# samd21_actuatorhub_pro_1_0_1_may2023.net
KiCad netlist of a schematic drawn in EAGLE
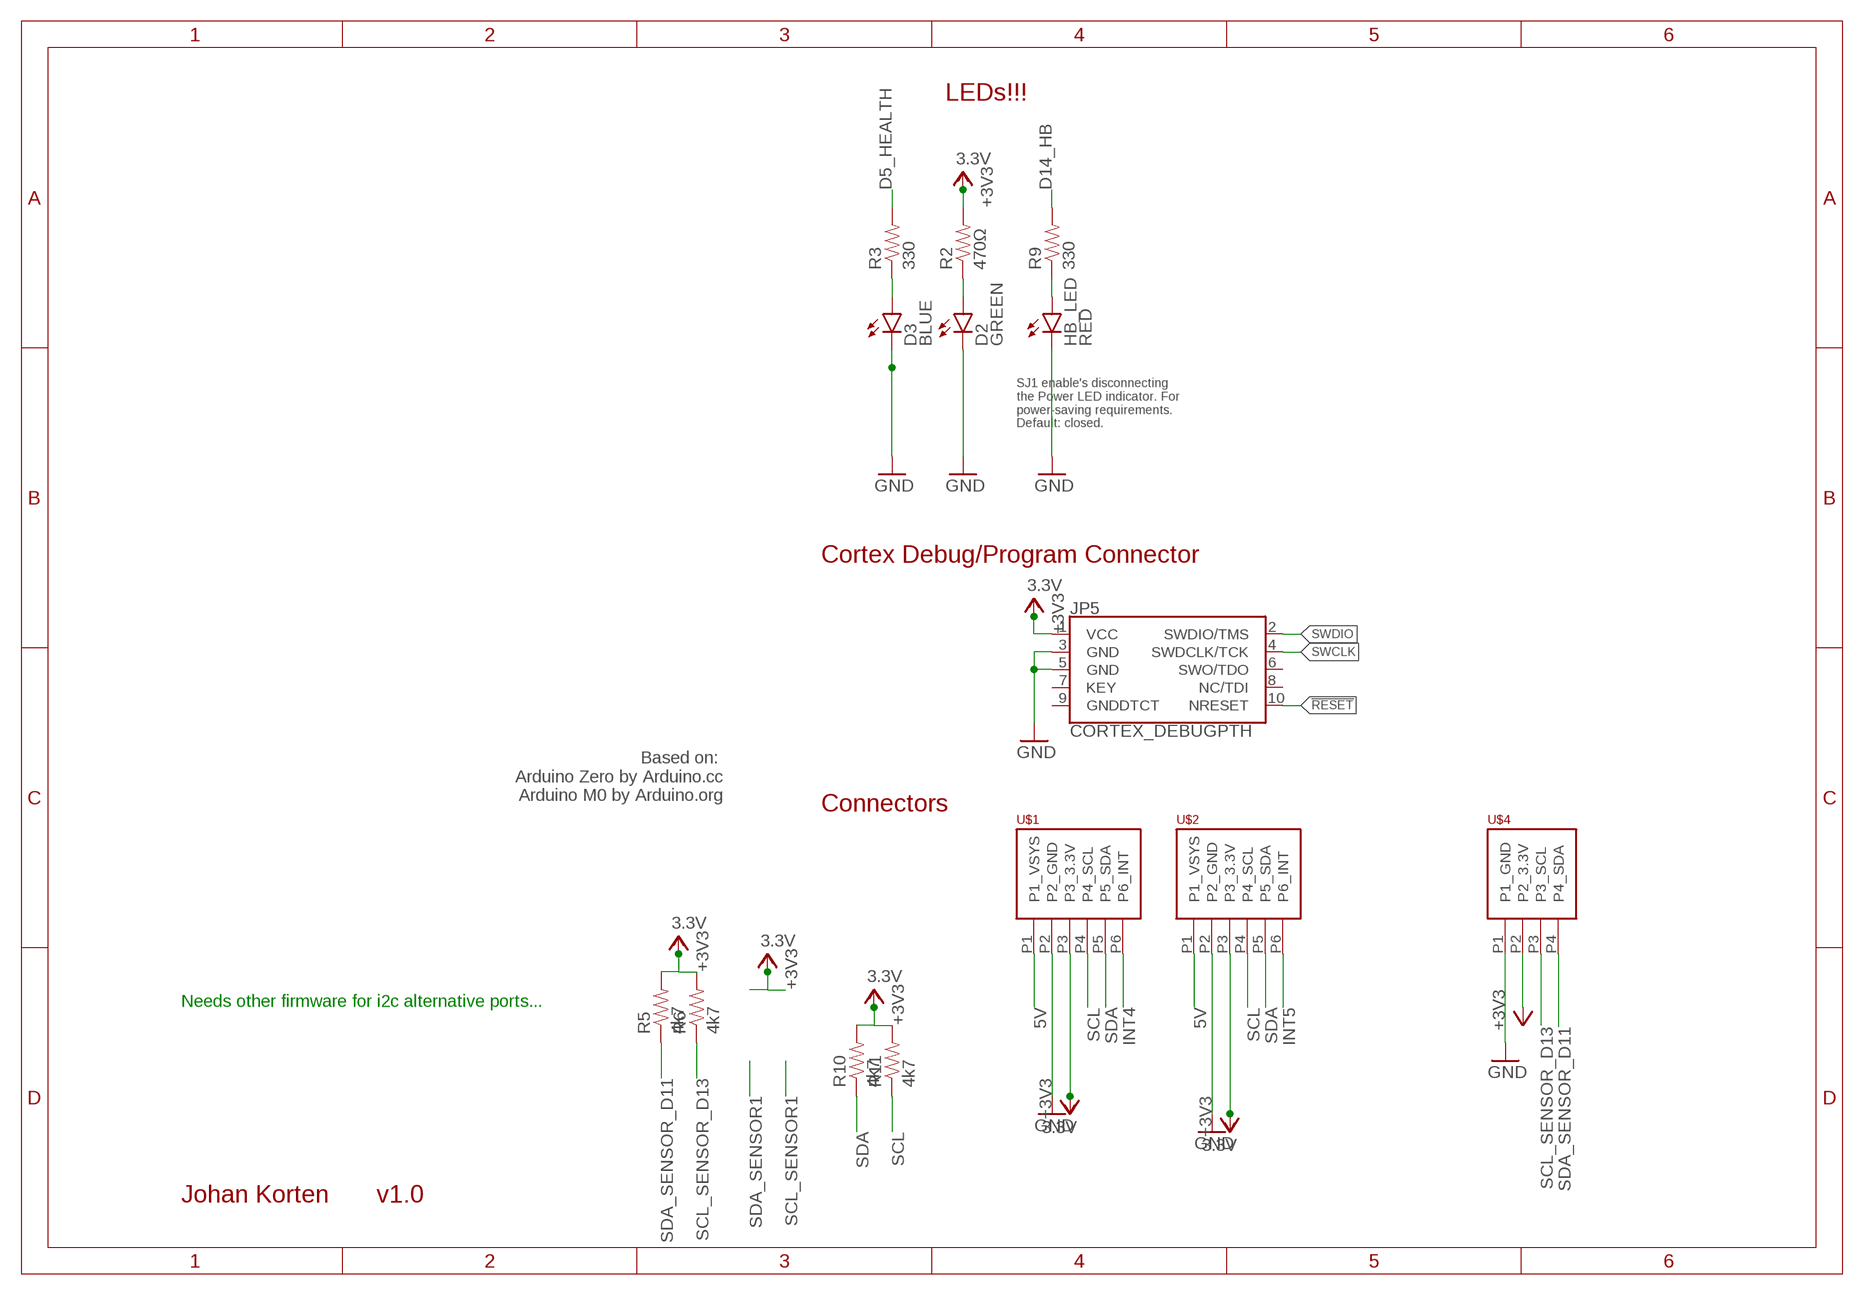
[diagram p0: schematic, sheet 1]
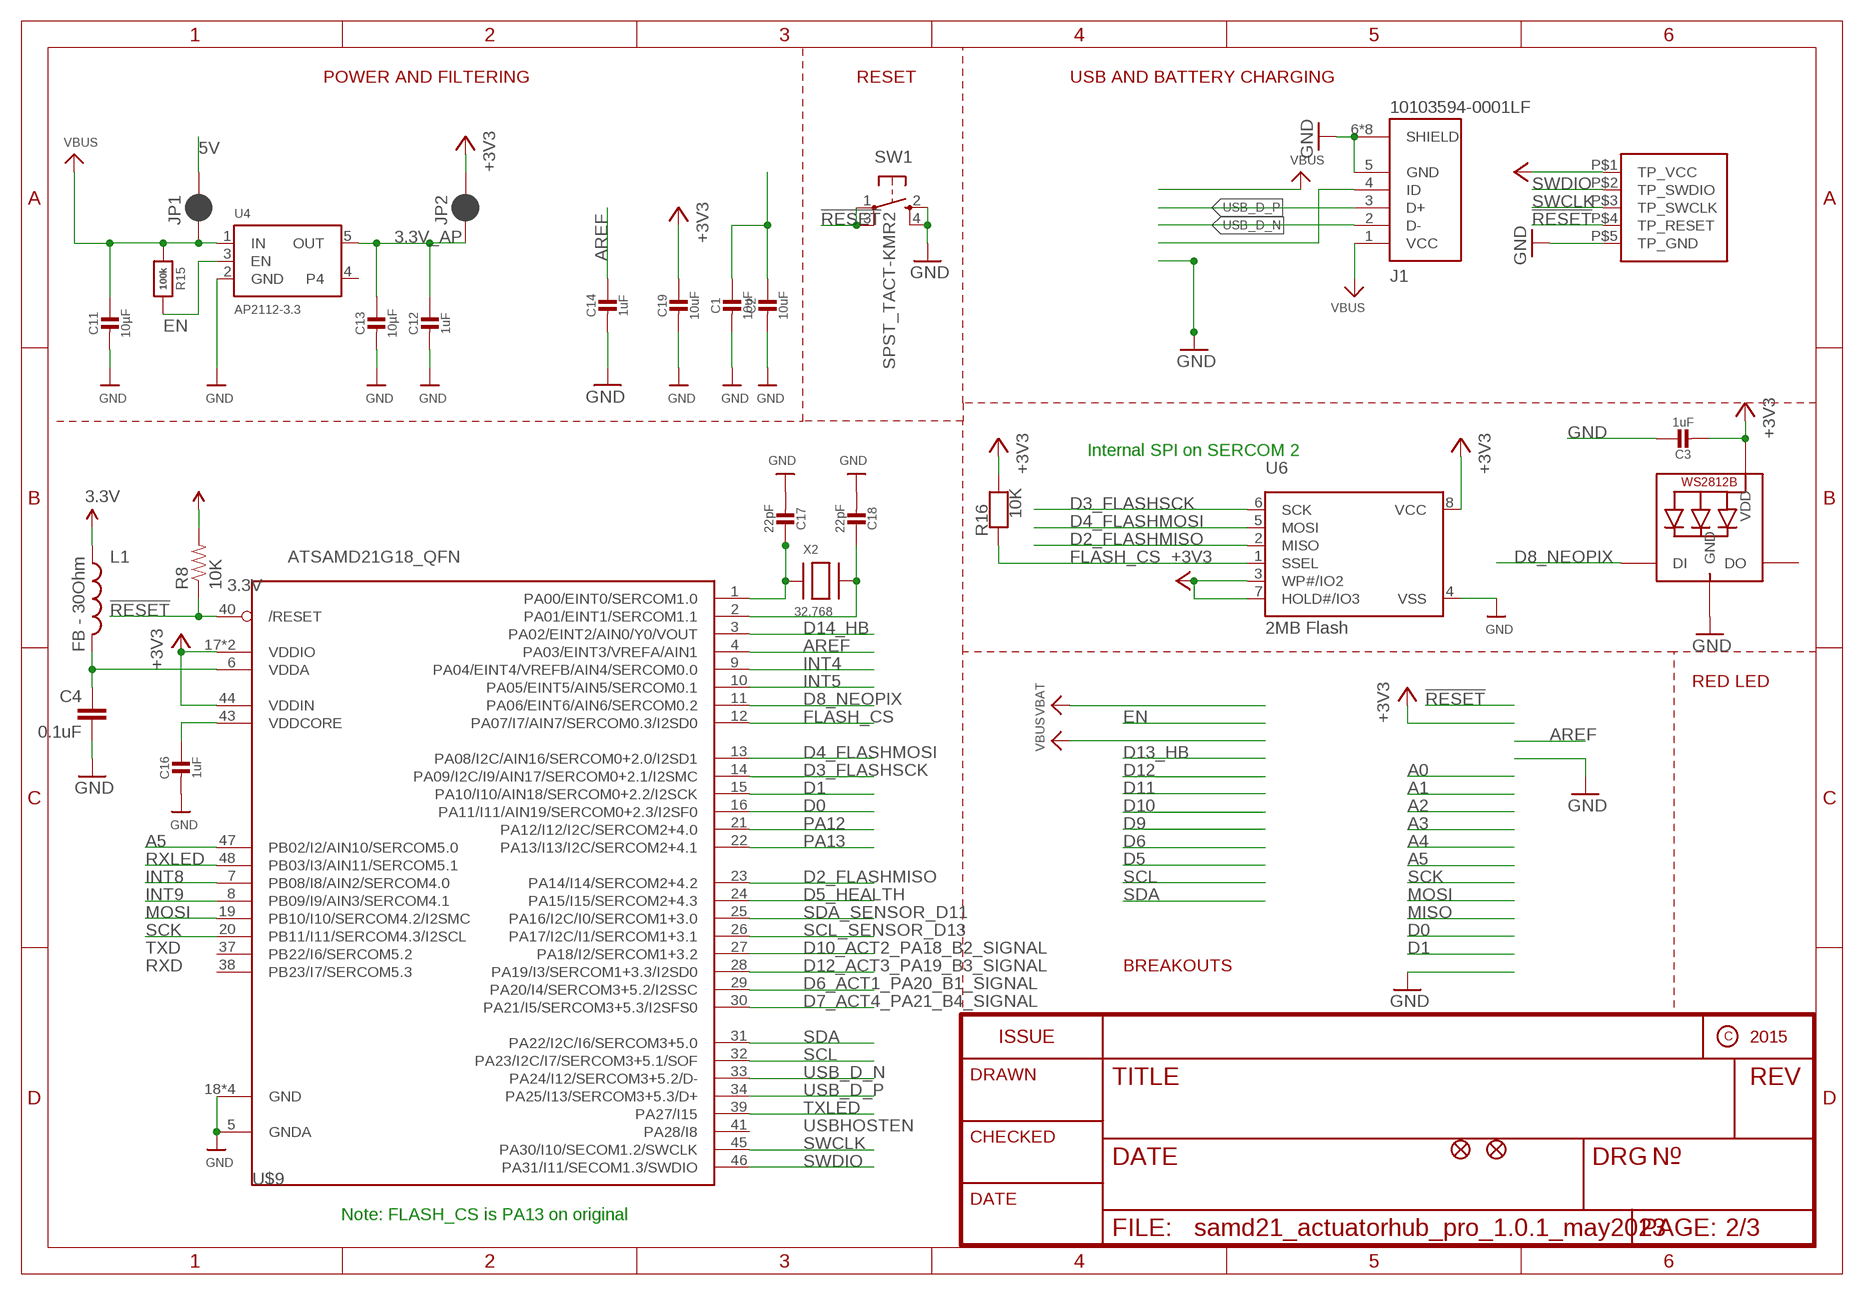
[diagram p1: schematic, sheet 2]
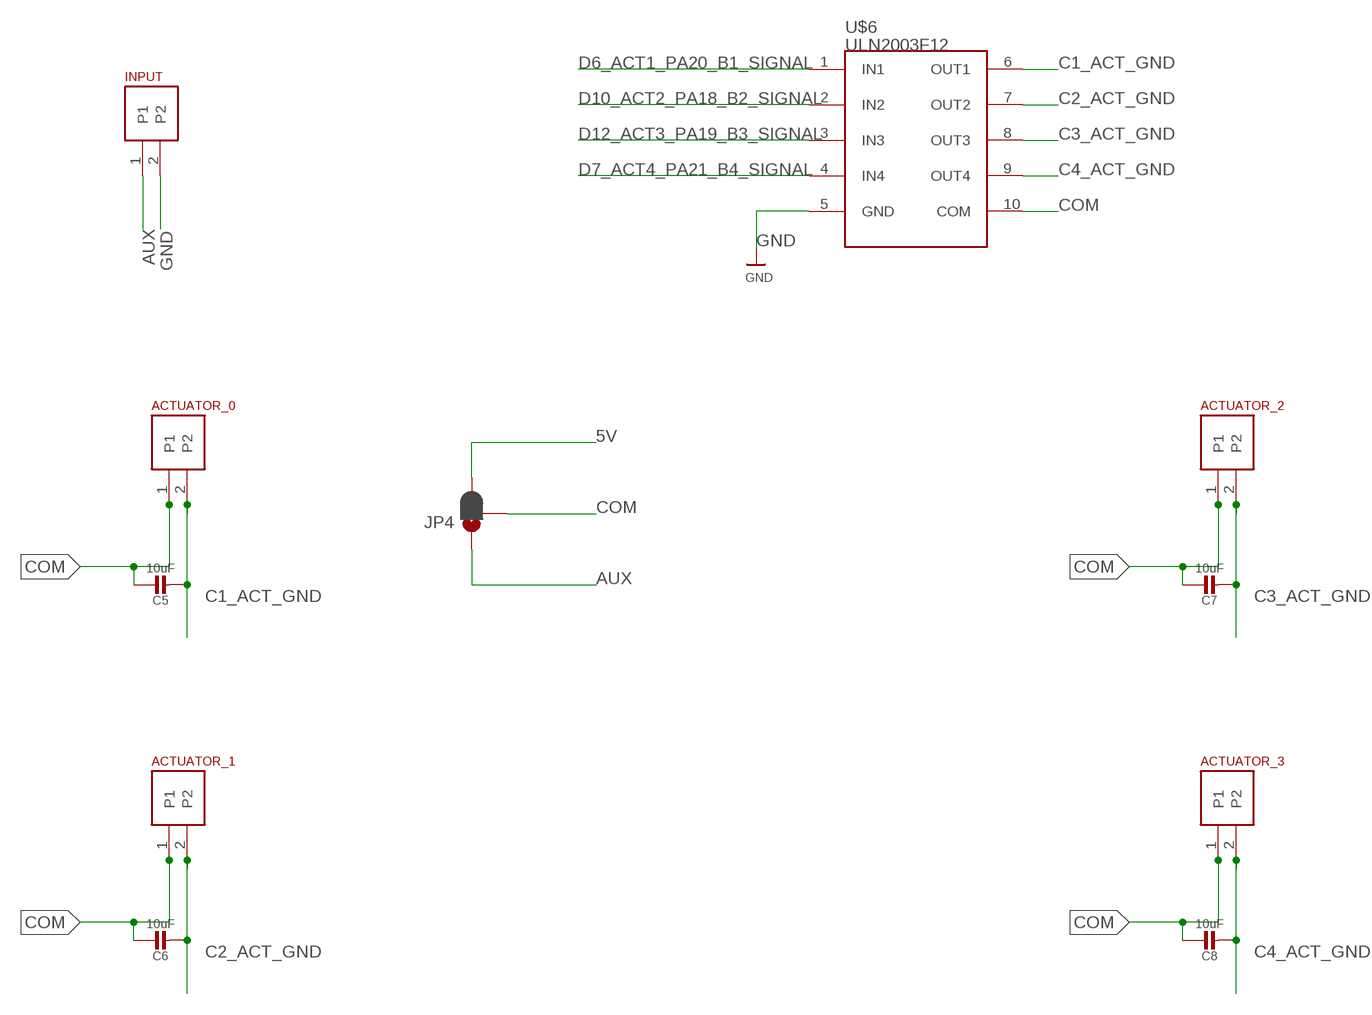
[diagram p2: schematic, sheet 3]

(export (version "E")
  (design (tool "Eeschema 10.0.6"))
  (components
    (comp (ref "ACTUATOR_0")
      (value "PHOENIX_PTSM_M2_TH")
      (footprint "eagle-import:PTSM_M2_THRHOLE")
      (libsource (lib "eagle-import") (part "PHOENIX_PTSM_M2_TH"))
    )
    (comp (ref "ACTUATOR_1")
      (value "PHOENIX_PTSM_M2_TH")
      (footprint "eagle-import:PTSM_M2_THRHOLE")
      (libsource (lib "eagle-import") (part "PHOENIX_PTSM_M2_TH"))
    )
    (comp (ref "ACTUATOR_2")
      (value "PHOENIX_PTSM_M2TH")
      (footprint "eagle-import:PTSM_M2_THRHOLE")
      (libsource (lib "eagle-import") (part "PHOENIX_PTSM_M2TH"))
    )
    (comp (ref "ACTUATOR_3")
      (value "PHOENIX_PTSM_M2TH")
      (footprint "eagle-import:PTSM_M2_THRHOLE")
      (libsource (lib "eagle-import") (part "PHOENIX_PTSM_M2TH"))
    )
    (comp (ref "C5")
      (value "10uF")
      (footprint "eagle-import:0805-NO")
      (libsource (lib "eagle-import") (part "CAP_CERAMIC0805-NOOUTLINE"))
    )
    (comp (ref "C6")
      (value "10uF")
      (footprint "eagle-import:0805-NO")
      (libsource (lib "eagle-import") (part "CAP_CERAMIC0805-NOOUTLINE"))
    )
    (comp (ref "C7")
      (value "10uF")
      (footprint "eagle-import:0805-NO")
      (libsource (lib "eagle-import") (part "CAP_CERAMIC0805-NOOUTLINE"))
    )
    (comp (ref "C8")
      (value "10uF")
      (footprint "eagle-import:0805-NO")
      (libsource (lib "eagle-import") (part "CAP_CERAMIC0805-NOOUTLINE"))
    )
    (comp (ref "INPUT")
      (value "PHOENIX_PTSM_M2_TH")
      (footprint "eagle-import:PTSM_M2_THRHOLE")
      (libsource (lib "eagle-import") (part "PHOENIX_PTSM_M2_TH"))
    )
    (comp (ref "JP4")
      (value "JUMPER-SMT_3_1-NC_PASTE_SILK")
      (footprint "eagle-import:SMT-JUMPER_3_1-NC_PASTE_SILK")
      (libsource (lib "eagle-import") (part "JUMPER-SMT_3_1-NC_PASTE_SILK"))
    )
    (comp (ref "U$6")
      (value "ULN2003F12")
      (footprint "eagle-import:U-DFN3030-10")
      (fields (field (name "MF") "Diodes Zetex"))
      (libsource (lib "eagle-import") (part "ULN2003F12"))
    )
    (comp (ref "D2")
      (value "GREEN")
      (footprint "eagle-import:LED-0603")
      (libsource (lib "eagle-import") (part "LED-RED0603"))
    )
    (comp (ref "D3")
      (value "BLUE")
      (footprint "eagle-import:LED-0603")
      (libsource (lib "eagle-import") (part "LED-BLUE0603"))
    )
    (comp (ref "HB_LED")
      (value "RED")
      (footprint "eagle-import:LED-0603")
      (libsource (lib "eagle-import") (part "LED-RED0603"))
    )
    (comp (ref "JP5")
      (value "CORTEX_DEBUGPTH")
      (footprint "eagle-import:2X5-PTH-1.27MM")
      (libsource (lib "eagle-import") (part "CORTEX_DEBUGPTH"))
    )
    (comp (ref "R2")
      (value "470Ω")
      (footprint "eagle-import:0603-RES")
      (libsource (lib "eagle-import") (part "330OHM1/10W1%(0603)"))
    )
    (comp (ref "R3")
      (value "330")
      (footprint "eagle-import:0603-RES")
      (libsource (lib "eagle-import") (part "330OHM1/10W1%(0603)"))
    )
    (comp (ref "R5")
      (value "4k7")
      (footprint "eagle-import:0603-RES")
      (libsource (lib "eagle-import") (part "330OHM1/10W1%(0603)"))
    )
    (comp (ref "R6")
      (value "4k7")
      (footprint "eagle-import:0603-RES")
      (libsource (lib "eagle-import") (part "330OHM1/10W1%(0603)"))
    )
    (comp (ref "R9")
      (value "330")
      (footprint "eagle-import:0603-RES")
      (libsource (lib "eagle-import") (part "330OHM1/10W1%(0603)"))
    )
    (comp (ref "R10")
      (value "4k7")
      (footprint "eagle-import:0603-RES")
      (libsource (lib "eagle-import") (part "330OHM1/10W1%(0603)"))
    )
    (comp (ref "R11")
      (value "4k7")
      (footprint "eagle-import:0603-RES")
      (libsource (lib "eagle-import") (part "330OHM1/10W1%(0603)"))
    )
    (comp (ref "U$1")
      (value "PHOENIX_PTSM_M6_TH_I2CPPANGLE")
      (footprint "eagle-import:PTSM_M6_THRHOLE")
      (libsource (lib "eagle-import") (part "PHOENIX_PTSM_M6_TH_I2CPPANGLE"))
    )
    (comp (ref "U$2")
      (value "PHOENIX_PTSM_M6_TH_I2CPPANGLE")
      (footprint "eagle-import:PTSM_M6_THRHOLE")
      (libsource (lib "eagle-import") (part "PHOENIX_PTSM_M6_TH_I2CPPANGLE"))
    )
    (comp (ref "U$4")
      (value "PHOENIX_PTSM_M4_THANGLE")
      (footprint "eagle-import:PTSM_M4_TH")
      (libsource (lib "eagle-import") (part "PHOENIX_PTSM_M4_THANGLE"))
    )
    (comp (ref "C1")
      (value "10uF")
      (footprint "eagle-import:0805-NO")
      (libsource (lib "eagle-import") (part "CAP_CERAMIC0805-NOOUTLINE"))
    )
    (comp (ref "C2")
      (value "10uF")
      (footprint "eagle-import:0805-NO")
      (libsource (lib "eagle-import") (part "CAP_CERAMIC0805-NOOUTLINE"))
    )
    (comp (ref "C3")
      (value "1uF")
      (footprint "eagle-import:0603-NO")
      (libsource (lib "eagle-import") (part "CAP_CERAMIC0603_NO"))
    )
    (comp (ref "C4")
      (value "0.1uF")
      (footprint "eagle-import:0402-CAP")
      (libsource (lib "eagle-import") (part "0.1UF-16V(+-10%)(0402)"))
    )
    (comp (ref "C11")
      (value "10µF")
      (footprint "eagle-import:0805-NO")
      (libsource (lib "eagle-import") (part "CAP_CERAMIC0805-NOOUTLINE"))
    )
    (comp (ref "C12")
      (value "1uF")
      (footprint "eagle-import:0603-NO")
      (libsource (lib "eagle-import") (part "CAP_CERAMIC0603_NO"))
    )
    (comp (ref "C13")
      (value "10µF")
      (footprint "eagle-import:0805-NO")
      (libsource (lib "eagle-import") (part "CAP_CERAMIC0805-NOOUTLINE"))
    )
    (comp (ref "C14")
      (value "1uF")
      (footprint "eagle-import:0603-NO")
      (libsource (lib "eagle-import") (part "CAP_CERAMIC0603_NO"))
    )
    (comp (ref "C16")
      (value "1uF")
      (footprint "eagle-import:0603-NO")
      (libsource (lib "eagle-import") (part "CAP_CERAMIC0603_NO"))
    )
    (comp (ref "C17")
      (value "22pF")
      (footprint "eagle-import:0603-NO")
      (libsource (lib "eagle-import") (part "CAP_CERAMIC0603_NO"))
    )
    (comp (ref "C18")
      (value "22pF")
      (footprint "eagle-import:0603-NO")
      (libsource (lib "eagle-import") (part "CAP_CERAMIC0603_NO"))
    )
    (comp (ref "C19")
      (value "10uF")
      (footprint "eagle-import:0805-NO")
      (libsource (lib "eagle-import") (part "CAP_CERAMIC0805-NOOUTLINE"))
    )
    (comp (ref "J1")
      (value "10103594-0001LF")
      (footprint "eagle-import:AMPHENOL_10103594-0001LF")
      (fields (field (name "MF") "AMPHENOL ICC / FCI"))
      (libsource (lib "eagle-import") (part "10103594-0001LF"))
    )
    (comp (ref "JP1")
      (value "JUMPER-SMT_2_NC_PASTE_SILK")
      (footprint "eagle-import:SMT-JUMPER_2_NC_PASTE_SILK")
      (libsource (lib "eagle-import") (part "JUMPER-SMT_2_NC_PASTE_SILK"))
    )
    (comp (ref "JP2")
      (value "JUMPER-SMT_2_NC_PASTE_SILK")
      (footprint "eagle-import:SMT-JUMPER_2_NC_PASTE_SILK")
      (libsource (lib "eagle-import") (part "JUMPER-SMT_2_NC_PASTE_SILK"))
    )
    (comp (ref "L1")
      (value "FB - 30Ohm")
      (footprint "eagle-import:0603")
      (libsource (lib "eagle-import") (part "INDUCTOR0603"))
    )
    (comp (ref "LED1")
      (value "WS2812B3535")
      (footprint "eagle-import:LED3535")
      (libsource (lib "eagle-import") (part "WS2812B3535"))
    )
    (comp (ref "R8")
      (value "10K")
      (footprint "eagle-import:0603-RES")
      (libsource (lib "eagle-import") (part "10KOHM-1/10W-1%(0603)0603"))
    )
    (comp (ref "R15")
      (value "100k")
      (footprint "eagle-import:0603-NO")
      (libsource (lib "eagle-import") (part "RESISTOR_0603_NOOUT"))
    )
    (comp (ref "R16")
      (value "10K")
      (footprint "eagle-import:0603-NO")
      (libsource (lib "eagle-import") (part "RESISTOR_0603_NOOUT"))
    )
    (comp (ref "SW1")
      (value "SPST_TACT-KMR2")
      (footprint "eagle-import:KMR2")
      (libsource (lib "eagle-import") (part "SPST_TACT-KMR2"))
    )
    (comp (ref "U$5")
      (value "HUB_TESTPINSHUBS")
      (footprint "eagle-import:TEST_PINS")
      (libsource (lib "eagle-import") (part "HUB_TESTPINSHUBS"))
    )
    (comp (ref "U$9")
      (value "ATSAMD21G18_QFN")
      (footprint "eagle-import:TQFN48_7MM")
      (libsource (lib "eagle-import") (part "ATSAMD21G_QFN"))
    )
    (comp (ref "U$34")
      (value "FIDUCIAL\"\"")
      (footprint "eagle-import:FIDUCIAL_1MM")
      (libsource (lib "eagle-import") (part "FIDUCIAL{dblquote}{dblquote}"))
    )
    (comp (ref "U$35")
      (value "FIDUCIAL\"\"")
      (footprint "eagle-import:FIDUCIAL_1MM")
      (libsource (lib "eagle-import") (part "FIDUCIAL{dblquote}{dblquote}"))
    )
    (comp (ref "U4")
      (value "AP2112-3.3")
      (footprint "eagle-import:SOT23-5")
      (libsource (lib "eagle-import") (part "VREG_SOT23-5"))
    )
    (comp (ref "U6")
      (value "2MB Flash")
      (footprint "eagle-import:SOIC8_208MIL")
      (libsource (lib "eagle-import") (part "SPIFLASH_SOIC8208MIL"))
    )
    (comp (ref "X2")
      (value "32.768")
      (footprint "eagle-import:XTAL3215")
      (libsource (lib "eagle-import") (part "XTAL-3.2X1.5"))
    )
  )
  (nets
    (net (code "1") (name "+3V3") (class "Default")
      (node (ref "C19") (pin "1") (pinfunction "1_1") (pintype "passive"))
      (node (ref "C3") (pin "2") (pinfunction "2_2") (pintype "passive"))
      (node (ref "JP2") (pin "2") (pinfunction "2_2") (pintype "passive"))
      (node (ref "JP5") (pin "1") (pinfunction "VCC_1") (pintype "bidirectional"))
      (node (ref "L1") (pin "1") (pinfunction "1_1") (pintype "passive"))
      (node (ref "LED1") (pin "2") (pinfunction "VDD_2") (pintype "power_in"))
      (node (ref "R10") (pin "2") (pinfunction "2_2") (pintype "passive"))
      (node (ref "R11") (pin "2") (pinfunction "2_2") (pintype "passive"))
      (node (ref "R16") (pin "2") (pinfunction "2_2") (pintype "passive"))
      (node (ref "R2") (pin "2") (pinfunction "2_2") (pintype "passive"))
      (node (ref "R5") (pin "2") (pinfunction "2_2") (pintype "passive"))
      (node (ref "R6") (pin "2") (pinfunction "2_2") (pintype "passive"))
      (node (ref "R8") (pin "2") (pinfunction "2_2") (pintype "passive"))
      (node (ref "U$1") (pin "P3") (pinfunction "P3_3.3V_P3") (pintype "power_in"))
      (node (ref "U$2") (pin "P3") (pinfunction "P3_3.3V_P3") (pintype "power_in"))
      (node (ref "U$4") (pin "P2") (pinfunction "P2_3.3V_P2") (pintype "power_in"))
      (node (ref "U$5") (pin "P$1") (pinfunction "TP_VCC_P$1") (pintype "bidirectional"))
      (node (ref "U$9") (pin "17") (pinfunction "VDDIO_17") (pintype "power_in"))
      (node (ref "U$9") (pin "36") (pinfunction "VDDIO_36") (pintype "power_in"))
      (node (ref "U$9") (pin "44") (pinfunction "VDDIN_44") (pintype "power_in"))
      (node (ref "U6") (pin "3") (pinfunction "WP#/IO2_3") (pintype "bidirectional"))
      (node (ref "U6") (pin "7") (pinfunction "HOLD#/IO3_7") (pintype "bidirectional"))
      (node (ref "U6") (pin "8") (pinfunction "VCC_8") (pintype "bidirectional"))
    )
    (net (code "2") (name "3.3V_AP") (class "Default")
      (node (ref "C12") (pin "1") (pinfunction "1_1") (pintype "passive"))
      (node (ref "C13") (pin "1") (pinfunction "1_1") (pintype "passive"))
      (node (ref "JP2") (pin "1") (pinfunction "1_1") (pintype "passive"))
      (node (ref "U4") (pin "5") (pinfunction "OUT_5") (pintype "power_in"))
    )
    (net (code "3") (name "5V") (class "Default")
      (node (ref "C1") (pin "1") (pinfunction "1_1") (pintype "passive"))
      (node (ref "C2") (pin "1") (pinfunction "1_1") (pintype "passive"))
      (node (ref "JP1") (pin "2") (pinfunction "2_2") (pintype "passive"))
      (node (ref "JP4") (pin "3") (pinfunction "3_3") (pintype "passive"))
      (node (ref "U$1") (pin "P1") (pinfunction "P1_VSYS_P1") (pintype "power_in"))
      (node (ref "U$2") (pin "P1") (pinfunction "P1_VSYS_P1") (pintype "power_in"))
    )
    (net (code "9") (name "A5") (class "Default")
      (node (ref "U$9") (pin "47") (pinfunction "PB02/I2/AIN10/SERCOM5.0_47") (pintype "bidirectional"))
    )
    (net (code "10") (name "AREF") (class "Default")
      (node (ref "C14") (pin "1") (pinfunction "1_1") (pintype "passive"))
      (node (ref "U$9") (pin "4") (pinfunction "PA03/EINT3/VREFA/AIN1_4") (pintype "bidirectional"))
    )
    (net (code "11") (name "AUX") (class "Default")
      (node (ref "INPUT") (pin "1") (pinfunction "P1_1") (pintype "bidirectional"))
      (node (ref "JP4") (pin "1") (pinfunction "1_1") (pintype "passive"))
    )
    (net (code "12") (name "C1_ACT_GND") (class "Default")
      (node (ref "ACTUATOR_0") (pin "2") (pinfunction "P2_2") (pintype "bidirectional"))
      (node (ref "C5") (pin "2") (pinfunction "2_2") (pintype "passive"))
      (node (ref "U$6") (pin "6") (pinfunction "OUT1_6") (pintype "bidirectional"))
    )
    (net (code "13") (name "C2_ACT_GND") (class "Default")
      (node (ref "ACTUATOR_1") (pin "2") (pinfunction "P2_2") (pintype "bidirectional"))
      (node (ref "C6") (pin "2") (pinfunction "2_2") (pintype "passive"))
      (node (ref "U$6") (pin "7") (pinfunction "OUT2_7") (pintype "bidirectional"))
    )
    (net (code "14") (name "C3_ACT_GND") (class "Default")
      (node (ref "ACTUATOR_2") (pin "2") (pinfunction "P2_2") (pintype "bidirectional"))
      (node (ref "C7") (pin "2") (pinfunction "2_2") (pintype "passive"))
      (node (ref "U$6") (pin "8") (pinfunction "OUT3_8") (pintype "bidirectional"))
    )
    (net (code "15") (name "C4_ACT_GND") (class "Default")
      (node (ref "ACTUATOR_3") (pin "2") (pinfunction "P2_2") (pintype "bidirectional"))
      (node (ref "C8") (pin "2") (pinfunction "2_2") (pintype "passive"))
      (node (ref "U$6") (pin "9") (pinfunction "OUT4_9") (pintype "bidirectional"))
    )
    (net (code "16") (name "COM") (class "Default")
      (node (ref "ACTUATOR_0") (pin "1") (pinfunction "P1_1") (pintype "bidirectional"))
      (node (ref "ACTUATOR_1") (pin "1") (pinfunction "P1_1") (pintype "bidirectional"))
      (node (ref "ACTUATOR_2") (pin "1") (pinfunction "P1_1") (pintype "bidirectional"))
      (node (ref "ACTUATOR_3") (pin "1") (pinfunction "P1_1") (pintype "bidirectional"))
      (node (ref "C5") (pin "1") (pinfunction "1_1") (pintype "passive"))
      (node (ref "C6") (pin "1") (pinfunction "1_1") (pintype "passive"))
      (node (ref "C7") (pin "1") (pinfunction "1_1") (pintype "passive"))
      (node (ref "C8") (pin "1") (pinfunction "1_1") (pintype "passive"))
      (node (ref "JP4") (pin "2") (pinfunction "2_2") (pintype "passive"))
      (node (ref "U$6") (pin "10") (pinfunction "COM_10") (pintype "bidirectional"))
    )
    (net (code "17") (name "D0") (class "Default")
      (node (ref "U$9") (pin "16") (pinfunction "PA11/I11/AIN19/SERCOM0+2.3/I2SF0_16") (pintype "bidirectional"))
    )
    (net (code "18") (name "D1") (class "Default")
      (node (ref "U$9") (pin "15") (pinfunction "PA10/I10/AIN18/SERCOM0+2.2/I2SCK_15") (pintype "bidirectional"))
    )
    (net (code "19") (name "D2_FLASHMISO") (class "Default")
      (node (ref "U$9") (pin "23") (pinfunction "PA14/I14/SERCOM2+4.2_23") (pintype "bidirectional"))
      (node (ref "U6") (pin "2") (pinfunction "MISO_2") (pintype "bidirectional"))
    )
    (net (code "20") (name "D3_FLASHSCK") (class "Default")
      (node (ref "U$9") (pin "14") (pinfunction "PA09/I2C/I9/AIN17/SERCOM0+2.1/I2SMC_14") (pintype "bidirectional"))
      (node (ref "U6") (pin "6") (pinfunction "SCK_6") (pintype "bidirectional"))
    )
    (net (code "21") (name "D4_FLASHMOSI") (class "Default")
      (node (ref "U$9") (pin "13") (pinfunction "PA08/I2C/AIN16/SERCOM0+2.0/I2SD1_13") (pintype "bidirectional"))
      (node (ref "U6") (pin "5") (pinfunction "MOSI_5") (pintype "bidirectional"))
    )
    (net (code "23") (name "D5_HEALTH") (class "Default")
      (node (ref "R3") (pin "2") (pinfunction "2_2") (pintype "passive"))
      (node (ref "U$9") (pin "24") (pinfunction "PA15/I15/SERCOM2+4.3_24") (pintype "bidirectional"))
    )
    (net (code "25") (name "D6_ACT1_PA20_B1_SIGNAL") (class "Default")
      (node (ref "U$6") (pin "1") (pinfunction "IN1_1") (pintype "bidirectional"))
      (node (ref "U$9") (pin "29") (pinfunction "PA20/I4/SERCOM3+5.2/I2SSC_29") (pintype "bidirectional"))
    )
    (net (code "26") (name "D7_ACT4_PA21_B4_SIGNAL") (class "Default")
      (node (ref "U$6") (pin "4") (pinfunction "IN4_4") (pintype "bidirectional"))
      (node (ref "U$9") (pin "30") (pinfunction "PA21/I5/SERCOM3+5.3/I2SFS0_30") (pintype "bidirectional"))
    )
    (net (code "27") (name "D8_NEOPIX") (class "Default")
      (node (ref "LED1") (pin "1") (pinfunction "DI_1") (pintype "input"))
      (node (ref "U$9") (pin "11") (pinfunction "PA06/EINT6/AIN6/SERCOM0.2_11") (pintype "bidirectional"))
    )
    (net (code "30") (name "D10_ACT2_PA18_B2_SIGNAL") (class "Default")
      (node (ref "U$6") (pin "2") (pinfunction "IN2_2") (pintype "bidirectional"))
      (node (ref "U$9") (pin "27") (pinfunction "PA18/I2/SERCOM1+3.2_27") (pintype "bidirectional"))
    )
    (net (code "33") (name "D12_ACT3_PA19_B3_SIGNAL") (class "Default")
      (node (ref "U$6") (pin "3") (pinfunction "IN3_3") (pintype "bidirectional"))
      (node (ref "U$9") (pin "28") (pinfunction "PA19/I3/SERCOM1+3.3/I2SD0_28") (pintype "bidirectional"))
    )
    (net (code "35") (name "D14_HB") (class "Default")
      (node (ref "R9") (pin "2") (pinfunction "2_2") (pintype "passive"))
      (node (ref "U$9") (pin "3") (pinfunction "PA02/EINT2/AIN0/Y0/VOUT_3") (pintype "bidirectional"))
    )
    (net (code "36") (name "EN") (class "Default")
      (node (ref "R15") (pin "2") (pinfunction "2_2") (pintype "passive"))
      (node (ref "U4") (pin "3") (pinfunction "EN_3") (pintype "input"))
    )
    (net (code "37") (name "FLASH_CS") (class "Default")
      (node (ref "R16") (pin "1") (pinfunction "1_1") (pintype "passive"))
      (node (ref "U$9") (pin "12") (pinfunction "PA07/I7/AIN7/SERCOM0.3/I2SD0_12") (pintype "bidirectional"))
      (node (ref "U6") (pin "1") (pinfunction "SSEL_1") (pintype "bidirectional"))
    )
    (net (code "38") (name "GND") (class "Default")
      (node (ref "C1") (pin "2") (pinfunction "2_2") (pintype "passive"))
      (node (ref "C11") (pin "2") (pinfunction "2_2") (pintype "passive"))
      (node (ref "C12") (pin "2") (pinfunction "2_2") (pintype "passive"))
      (node (ref "C13") (pin "2") (pinfunction "2_2") (pintype "passive"))
      (node (ref "C14") (pin "2") (pinfunction "2_2") (pintype "passive"))
      (node (ref "C16") (pin "2") (pinfunction "2_2") (pintype "passive"))
      (node (ref "C17") (pin "2") (pinfunction "2_2") (pintype "passive"))
      (node (ref "C18") (pin "2") (pinfunction "2_2") (pintype "passive"))
      (node (ref "C19") (pin "2") (pinfunction "2_2") (pintype "passive"))
      (node (ref "C2") (pin "2") (pinfunction "2_2") (pintype "passive"))
      (node (ref "C3") (pin "1") (pinfunction "1_1") (pintype "passive"))
      (node (ref "C4") (pin "2") (pinfunction "2_2") (pintype "passive"))
      (node (ref "D2") (pin "C") (pinfunction "C_C") (pintype "passive"))
      (node (ref "D3") (pin "C") (pinfunction "C_C") (pintype "passive"))
      (node (ref "HB_LED") (pin "C") (pinfunction "C_C") (pintype "passive"))
      (node (ref "INPUT") (pin "2") (pinfunction "P2_2") (pintype "bidirectional"))
      (node (ref "J1") (pin "10") (pinfunction "SHIELD_10") (pintype "passive"))
      (node (ref "J1") (pin "11") (pinfunction "SHIELD_11") (pintype "passive"))
      (node (ref "J1") (pin "5") (pinfunction "GND_5") (pintype "power_in"))
      (node (ref "J1") (pin "6") (pinfunction "SHIELD_6") (pintype "passive"))
      (node (ref "J1") (pin "7") (pinfunction "SHIELD_7") (pintype "passive"))
      (node (ref "J1") (pin "8") (pinfunction "SHIELD_8") (pintype "passive"))
      (node (ref "J1") (pin "9") (pinfunction "SHIELD_9") (pintype "passive"))
      (node (ref "J1") (pin "S1") (pinfunction "SHIELD_S1") (pintype "passive"))
      (node (ref "J1") (pin "S2") (pinfunction "SHIELD_S2") (pintype "passive"))
      (node (ref "JP5") (pin "3") (pinfunction "GND_3") (pintype "bidirectional"))
      (node (ref "JP5") (pin "5") (pinfunction "GND_5") (pintype "bidirectional"))
      (node (ref "LED1") (pin "4") (pinfunction "GND_4") (pintype "power_in"))
      (node (ref "SW1") (pin "2") (pinfunction "S_2") (pintype "passive"))
      (node (ref "SW1") (pin "4") (pinfunction "S1_4") (pintype "passive"))
      (node (ref "U$1") (pin "P2") (pinfunction "P2_GND_P2") (pintype "power_in"))
      (node (ref "U$2") (pin "P2") (pinfunction "P2_GND_P2") (pintype "power_in"))
      (node (ref "U$4") (pin "P1") (pinfunction "P1_GND_P1") (pintype "power_in"))
      (node (ref "U$5") (pin "P$5") (pinfunction "TP_GND_P$5") (pintype "bidirectional"))
      (node (ref "U$6") (pin "5") (pinfunction "GND_5") (pintype "bidirectional"))
      (node (ref "U$9") (pin "18") (pinfunction "GND_18") (pintype "power_in"))
      (node (ref "U$9") (pin "35") (pinfunction "GND_35") (pintype "power_in"))
      (node (ref "U$9") (pin "42") (pinfunction "GND_42") (pintype "power_in"))
      (node (ref "U$9") (pin "5") (pinfunction "GNDA_5") (pintype "power_in"))
      (node (ref "U$9") (pin "THERMAL") (pinfunction "GND_THERMAL") (pintype "power_in"))
      (node (ref "U4") (pin "2") (pinfunction "GND_2") (pintype "power_in"))
      (node (ref "U6") (pin "4") (pinfunction "VSS_4") (pintype "bidirectional"))
    )
    (net (code "39") (name "INT4") (class "Default")
      (node (ref "U$1") (pin "P6") (pinfunction "P6_INT_P6") (pintype "power_in"))
      (node (ref "U$9") (pin "9") (pinfunction "PA04/EINT4/VREFB/AIN4/SERCOM0.0_9") (pintype "bidirectional"))
    )
    (net (code "40") (name "INT5") (class "Default")
      (node (ref "U$2") (pin "P6") (pinfunction "P6_INT_P6") (pintype "power_in"))
      (node (ref "U$9") (pin "10") (pinfunction "PA05/EINT5/AIN5/SERCOM0.1_10") (pintype "bidirectional"))
    )
    (net (code "41") (name "INT8") (class "Default")
      (node (ref "U$9") (pin "7") (pinfunction "PB08/I8/AIN2/SERCOM4.0_7") (pintype "bidirectional"))
    )
    (net (code "42") (name "INT9") (class "Default")
      (node (ref "U$9") (pin "8") (pinfunction "PB09/I9/AIN3/SERCOM4.1_8") (pintype "bidirectional"))
    )
    (net (code "44") (name "MOSI") (class "Default")
      (node (ref "U$9") (pin "19") (pinfunction "PB10/I10/SERCOM4.2/I2SMC_19") (pintype "bidirectional"))
    )
    (net (code "45") (name "Net-(D2-PadA)") (class "Default")
      (node (ref "D2") (pin "A") (pinfunction "A_A") (pintype "passive"))
      (node (ref "R2") (pin "1") (pinfunction "1_1") (pintype "passive"))
    )
    (net (code "46") (name "Net-(D3-PadA)") (class "Default")
      (node (ref "D3") (pin "A") (pinfunction "A_A") (pintype "passive"))
      (node (ref "R3") (pin "1") (pinfunction "1_1") (pintype "passive"))
    )
    (net (code "47") (name "Net-(HB_LED-PadA)") (class "Default")
      (node (ref "HB_LED") (pin "A") (pinfunction "A_A") (pintype "passive"))
      (node (ref "R9") (pin "1") (pinfunction "1_1") (pintype "passive"))
    )
    (net (code "48") (name "Net-(U$9-PA00{slash}EINT0{slash}SERCOM1.0)") (class "Default")
      (node (ref "C17") (pin "1") (pinfunction "1_1") (pintype "passive"))
      (node (ref "U$9") (pin "1") (pinfunction "PA00/EINT0/SERCOM1.0_1") (pintype "bidirectional"))
      (node (ref "X2") (pin "P$1") (pinfunction "P$1_P$1") (pintype "bidirectional"))
    )
    (net (code "49") (name "Net-(U$9-PA01{slash}EINT1{slash}SERCOM1.1)") (class "Default")
      (node (ref "C18") (pin "1") (pinfunction "1_1") (pintype "passive"))
      (node (ref "U$9") (pin "2") (pinfunction "PA01/EINT1/SERCOM1.1_2") (pintype "bidirectional"))
      (node (ref "X2") (pin "P$2") (pinfunction "P$2_P$2") (pintype "bidirectional"))
    )
    (net (code "50") (name "Net-(U$9-VDDA)") (class "Default")
      (node (ref "C4") (pin "1") (pinfunction "1_1") (pintype "passive"))
      (node (ref "L1") (pin "2") (pinfunction "2_2") (pintype "passive"))
      (node (ref "U$9") (pin "6") (pinfunction "VDDA_6") (pintype "power_in"))
    )
    (net (code "51") (name "Net-(U$9-VDDCORE)") (class "Default")
      (node (ref "C16") (pin "1") (pinfunction "1_1") (pintype "passive"))
      (node (ref "U$9") (pin "43") (pinfunction "VDDCORE_43") (pintype "power_in"))
    )
    (net (code "52") (name "PA12") (class "Default")
      (node (ref "U$9") (pin "21") (pinfunction "PA12/I12/I2C/SERCOM2+4.0_21") (pintype "bidirectional"))
    )
    (net (code "53") (name "PA13") (class "Default")
      (node (ref "U$9") (pin "22") (pinfunction "PA13/I13/I2C/SERCOM2+4.1_22") (pintype "bidirectional"))
    )
    (net (code "54") (name "RXLED") (class "Default")
      (node (ref "U$9") (pin "48") (pinfunction "PB03/I3/AIN11/SERCOM5.1_48") (pintype "bidirectional"))
    )
    (net (code "55") (name "SCK") (class "Default")
      (node (ref "U$9") (pin "20") (pinfunction "PB11/I11/SERCOM4.3/I2SCL_20") (pintype "bidirectional"))
    )
    (net (code "56") (name "SCL") (class "Default")
      (node (ref "R11") (pin "1") (pinfunction "1_1") (pintype "passive"))
      (node (ref "U$1") (pin "P4") (pinfunction "P4_SCL_P4") (pintype "bidirectional"))
      (node (ref "U$2") (pin "P4") (pinfunction "P4_SCL_P4") (pintype "bidirectional"))
      (node (ref "U$9") (pin "32") (pinfunction "PA23/I2C/I7/SERCOM3+5.1/SOF_32") (pintype "bidirectional"))
    )
    (net (code "58") (name "SCL_SENSOR_D13") (class "Default")
      (node (ref "R6") (pin "1") (pinfunction "1_1") (pintype "passive"))
      (node (ref "U$4") (pin "P3") (pinfunction "P3_SCL_P3") (pintype "bidirectional"))
      (node (ref "U$9") (pin "26") (pinfunction "PA17/I2C/I1/SERCOM1+3.1_26") (pintype "bidirectional"))
    )
    (net (code "59") (name "SDA") (class "Default")
      (node (ref "R10") (pin "1") (pinfunction "1_1") (pintype "passive"))
      (node (ref "U$1") (pin "P5") (pinfunction "P5_SDA_P5") (pintype "bidirectional"))
      (node (ref "U$2") (pin "P5") (pinfunction "P5_SDA_P5") (pintype "bidirectional"))
      (node (ref "U$9") (pin "31") (pinfunction "PA22/I2C/I6/SERCOM3+5.0_31") (pintype "bidirectional"))
    )
    (net (code "61") (name "SDA_SENSOR_D11") (class "Default")
      (node (ref "R5") (pin "1") (pinfunction "1_1") (pintype "passive"))
      (node (ref "U$4") (pin "P4") (pinfunction "P4_SDA_P4") (pintype "bidirectional"))
      (node (ref "U$9") (pin "25") (pinfunction "PA16/I2C/I0/SERCOM1+3.0_25") (pintype "bidirectional"))
    )
    (net (code "62") (name "SWCLK") (class "Default")
      (node (ref "JP5") (pin "4") (pinfunction "SWDCLK/TCK_4") (pintype "bidirectional"))
      (node (ref "U$5") (pin "P$3") (pinfunction "TP_SWCLK_P$3") (pintype "bidirectional"))
      (node (ref "U$9") (pin "45") (pinfunction "PA30/I10/SECOM1.2/SWCLK_45") (pintype "bidirectional"))
    )
    (net (code "63") (name "SWDIO") (class "Default")
      (node (ref "JP5") (pin "2") (pinfunction "SWDIO/TMS_2") (pintype "bidirectional"))
      (node (ref "U$5") (pin "P$2") (pinfunction "TP_SWDIO_P$2") (pintype "bidirectional"))
      (node (ref "U$9") (pin "46") (pinfunction "PA31/I11/SECOM1.3/SWDIO_46") (pintype "bidirectional"))
    )
    (net (code "64") (name "TXLED") (class "Default")
      (node (ref "U$9") (pin "39") (pinfunction "PA27/I15_39") (pintype "bidirectional"))
    )
    (net (code "65") (name "USB_D_N") (class "Default")
      (node (ref "J1") (pin "2") (pinfunction "D-_2") (pintype "bidirectional"))
      (node (ref "U$9") (pin "33") (pinfunction "PA24/I12/SERCOM3+5.2/D-_33") (pintype "bidirectional"))
    )
    (net (code "66") (name "USB_D_P") (class "Default")
      (node (ref "J1") (pin "3") (pinfunction "D+_3") (pintype "bidirectional"))
      (node (ref "U$9") (pin "34") (pinfunction "PA25/I13/SERCOM3+5.3/D+_34") (pintype "bidirectional"))
    )
    (net (code "68") (name "VBUS") (class "Default")
      (node (ref "C11") (pin "1") (pinfunction "1_1") (pintype "passive"))
      (node (ref "J1") (pin "1") (pinfunction "VCC_1") (pintype "power_in"))
      (node (ref "JP1") (pin "1") (pinfunction "1_1") (pintype "passive"))
      (node (ref "R15") (pin "1") (pinfunction "1_1") (pintype "passive"))
      (node (ref "U4") (pin "1") (pinfunction "IN_1") (pintype "power_in"))
    )
    (net (code "69") (name "unconnected-(J1-ID-Pad4)") (class "Default")
      (node (ref "J1") (pin "4") (pinfunction "ID_4") (pintype "bidirectional"))
    )
    (net (code "70") (name "unconnected-(JP5-GNDDTCT-Pad9)") (class "Default")
      (node (ref "JP5") (pin "9") (pinfunction "GNDDTCT_9") (pintype "bidirectional"))
    )
    (net (code "71") (name "unconnected-(JP5-KEY-Pad7)") (class "Default")
      (node (ref "JP5") (pin "7") (pinfunction "KEY_7") (pintype "bidirectional"))
    )
    (net (code "72") (name "unconnected-(JP5-NC{slash}TDI-Pad8)") (class "Default")
      (node (ref "JP5") (pin "8") (pinfunction "NC/TDI_8") (pintype "bidirectional"))
    )
    (net (code "73") (name "unconnected-(JP5-SWO{slash}TDO-Pad6)") (class "Default")
      (node (ref "JP5") (pin "6") (pinfunction "SWO/TDO_6") (pintype "bidirectional"))
    )
    (net (code "74") (name "unconnected-(LED1-DO-Pad3)") (class "Default")
      (node (ref "LED1") (pin "3") (pinfunction "DO_3") (pintype "output"))
    )
    (net (code "75") (name "unconnected-(U$9-PA28{slash}I8-Pad41)") (class "Default")
      (node (ref "U$9") (pin "41") (pinfunction "PA28/I8_41") (pintype "bidirectional"))
    )
    (net (code "76") (name "unconnected-(U$9-PB22{slash}I6{slash}SERCOM5.2-Pad37)") (class "Default")
      (node (ref "U$9") (pin "37") (pinfunction "PB22/I6/SERCOM5.2_37") (pintype "bidirectional"))
    )
    (net (code "77") (name "unconnected-(U$9-PB23{slash}I7{slash}SERCOM5.3-Pad38)") (class "Default")
      (node (ref "U$9") (pin "38") (pinfunction "PB23/I7/SERCOM5.3_38") (pintype "bidirectional"))
    )
    (net (code "78") (name "unconnected-(U4-P4-Pad4)") (class "Default")
      (node (ref "U4") (pin "4") (pinfunction "P4_4") (pintype "bidirectional"))
    )
    (net (code "79") (name "~{RESET}") (class "Default")
      (node (ref "JP5") (pin "10") (pinfunction "NRESET_10") (pintype "bidirectional"))
      (node (ref "R8") (pin "1") (pinfunction "1_1") (pintype "passive"))
      (node (ref "SW1") (pin "1") (pinfunction "P_1") (pintype "passive"))
      (node (ref "SW1") (pin "3") (pinfunction "P1_3") (pintype "passive"))
      (node (ref "U$5") (pin "P$4") (pinfunction "TP_RESET_P$4") (pintype "bidirectional"))
      (node (ref "U$9") (pin "40") (pinfunction "/RESET_40") (pintype "bidirectional"))
    )
  )
)
